# Sheet_1_2024-06-24.net
KiCad netlist of a schematic drawn in Altium Designer
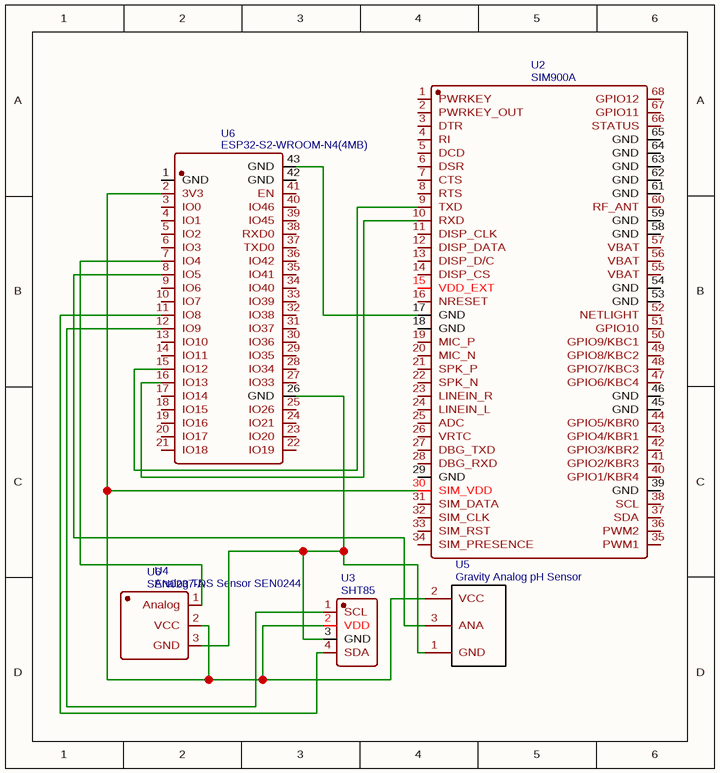
[diagram p0: Sheet_1_2024-06-24.schdoc]

(export (version "E")
  (design (tool "Eeschema 10.0.6"))
  (components
    (comp (ref "U2")
      (value "SIM900A")
      (fields (field (name "CONTRIBUTOR") "LCSC"))
      (libsource (lib "altium-import") (part "root_0_SIM900A_"))
    )
    (comp (ref "U3")
      (value "SHT85")
      (fields (field (name "CONTRIBUTOR") "zsamora"))
      (libsource (lib "altium-import") (part "root_0_SHT85_"))
    )
    (comp (ref "U4")
      (value "Analog TDS Sensor SEN0244")
      (fields (field (name "CONTRIBUTOR") "陳詩函"))
      (libsource (lib "altium-import") (part "root_0_Analog TDS Sensor SEN0244_"))
    )
    (comp (ref "U5")
      (value "Gravity Analog pH Sensor")
      (fields
        (field (name "MANUFACTURER") "Atlas Scientific")
        (field (name "MANUFACTURER PART") "GRV-pH")
        (field (name "CONTRIBUTOR") "ajannin82")
      )
      (libsource (lib "altium-import") (part "root_0_Gravity Analog pH Sensor_"))
    )
    (comp (ref "U6")
      (value "ESP32-S2-WROOM-N4(4MB)")
      (fields (field (name "MANUFACTURER") "ESPRESSIF(乐鑫)") (field (name "CONTRIBUTOR") "lcsc"))
      (libsource (lib "altium-import") (part "root_0_ESP32-S2-WROOM-N4(4MB)_"))
    )
  )
  (nets
    (net (code "1") (name "Net-(U2-GND-Pad17)") (class "Default")
      (node (ref "U2") (pin "17") (pinfunction "GND_17") (pintype "passive"))
      (node (ref "U6") (pin "43") (pinfunction "GND_43") (pintype "passive"))
    )
    (net (code "2") (name "Net-(U2-RXD)") (class "Default")
      (node (ref "U2") (pin "10") (pinfunction "RXD_10") (pintype "passive"))
      (node (ref "U6") (pin "16") (pinfunction "IO13_16") (pintype "passive"))
    )
    (net (code "3") (name "Net-(U2-SIM_VDD)") (class "Default")
      (node (ref "U2") (pin "30") (pinfunction "SIM_VDD_30") (pintype "passive"))
      (node (ref "U3") (pin "2") (pinfunction "VDD_2") (pintype "passive"))
      (node (ref "U4") (pin "2") (pinfunction "VCC_2") (pintype "passive"))
      (node (ref "U5") (pin "2") (pinfunction "VCC_2") (pintype "passive"))
      (node (ref "U6") (pin "2") (pinfunction "3V3_2") (pintype "passive"))
    )
    (net (code "4") (name "Net-(U2-TXD)") (class "Default")
      (node (ref "U2") (pin "9") (pinfunction "TXD_9") (pintype "passive"))
      (node (ref "U6") (pin "15") (pinfunction "IO12_15") (pintype "passive"))
    )
    (net (code "5") (name "Net-(U3-GND)") (class "Default")
      (node (ref "U3") (pin "3") (pinfunction "GND_3") (pintype "passive"))
      (node (ref "U4") (pin "3") (pinfunction "GND_3") (pintype "passive"))
      (node (ref "U5") (pin "1") (pinfunction "GND_1") (pintype "passive"))
      (node (ref "U6") (pin "26") (pinfunction "GND_26") (pintype "passive"))
    )
    (net (code "6") (name "Net-(U3-SCL)") (class "Default")
      (node (ref "U3") (pin "1") (pinfunction "SCL_1") (pintype "passive"))
      (node (ref "U6") (pin "12") (pinfunction "IO9_12") (pintype "passive"))
    )
    (net (code "7") (name "Net-(U3-SDA)") (class "Default")
      (node (ref "U3") (pin "4") (pinfunction "SDA_4") (pintype "passive"))
      (node (ref "U6") (pin "11") (pinfunction "IO8_11") (pintype "passive"))
    )
    (net (code "8") (name "Net-(U4-Analog)") (class "Default")
      (node (ref "U4") (pin "1") (pinfunction "Analog_1") (pintype "passive"))
      (node (ref "U6") (pin "7") (pinfunction "IO4_7") (pintype "passive"))
    )
    (net (code "9") (name "Net-(U5-ANA)") (class "Default")
      (node (ref "U5") (pin "3") (pinfunction "ANA_3") (pintype "passive"))
      (node (ref "U6") (pin "8") (pinfunction "IO5_8") (pintype "passive"))
    )
    (net (code "10") (name "unconnected-(U2-ADC-Pad25)") (class "Default")
      (node (ref "U2") (pin "25") (pinfunction "ADC_25") (pintype "passive"))
    )
    (net (code "11") (name "unconnected-(U2-CTS-Pad7)") (class "Default")
      (node (ref "U2") (pin "7") (pinfunction "CTS_7") (pintype "passive"))
    )
    (net (code "12") (name "unconnected-(U2-DBG_RXD-Pad28)") (class "Default")
      (node (ref "U2") (pin "28") (pinfunction "DBG_RXD_28") (pintype "passive"))
    )
    (net (code "13") (name "unconnected-(U2-DBG_TXD-Pad27)") (class "Default")
      (node (ref "U2") (pin "27") (pinfunction "DBG_TXD_27") (pintype "passive"))
    )
    (net (code "14") (name "unconnected-(U2-DCD-Pad5)") (class "Default")
      (node (ref "U2") (pin "5") (pinfunction "DCD_5") (pintype "passive"))
    )
    (net (code "15") (name "unconnected-(U2-DISP_CLK-Pad11)") (class "Default")
      (node (ref "U2") (pin "11") (pinfunction "DISP_CLK_11") (pintype "passive"))
    )
    (net (code "16") (name "unconnected-(U2-DISP_CS-Pad14)") (class "Default")
      (node (ref "U2") (pin "14") (pinfunction "DISP_CS_14") (pintype "passive"))
    )
    (net (code "17") (name "unconnected-(U2-DISP_DATA-Pad12)") (class "Default")
      (node (ref "U2") (pin "12") (pinfunction "DISP_DATA_12") (pintype "passive"))
    )
    (net (code "18") (name "unconnected-(U2-DISP_D{slash}C-Pad13)") (class "Default")
      (node (ref "U2") (pin "13") (pinfunction "DISP_D/C_13") (pintype "passive"))
    )
    (net (code "19") (name "unconnected-(U2-DSR-Pad6)") (class "Default")
      (node (ref "U2") (pin "6") (pinfunction "DSR_6") (pintype "passive"))
    )
    (net (code "20") (name "unconnected-(U2-DTR-Pad3)") (class "Default")
      (node (ref "U2") (pin "3") (pinfunction "DTR_3") (pintype "passive"))
    )
    (net (code "21") (name "unconnected-(U2-GND-Pad18)") (class "Default")
      (node (ref "U2") (pin "18") (pinfunction "GND_18") (pintype "passive"))
    )
    (net (code "22") (name "unconnected-(U2-GND-Pad29)") (class "Default")
      (node (ref "U2") (pin "29") (pinfunction "GND_29") (pintype "passive"))
    )
    (net (code "23") (name "unconnected-(U2-GND-Pad39)") (class "Default")
      (node (ref "U2") (pin "39") (pinfunction "GND_39") (pintype "passive"))
    )
    (net (code "24") (name "unconnected-(U2-GND-Pad45)") (class "Default")
      (node (ref "U2") (pin "45") (pinfunction "GND_45") (pintype "passive"))
    )
    (net (code "25") (name "unconnected-(U2-GND-Pad46)") (class "Default")
      (node (ref "U2") (pin "46") (pinfunction "GND_46") (pintype "passive"))
    )
    (net (code "26") (name "unconnected-(U2-GND-Pad53)") (class "Default")
      (node (ref "U2") (pin "53") (pinfunction "GND_53") (pintype "passive"))
    )
    (net (code "27") (name "unconnected-(U2-GND-Pad54)") (class "Default")
      (node (ref "U2") (pin "54") (pinfunction "GND_54") (pintype "passive"))
    )
    (net (code "28") (name "unconnected-(U2-GND-Pad58)") (class "Default")
      (node (ref "U2") (pin "58") (pinfunction "GND_58") (pintype "passive"))
    )
    (net (code "29") (name "unconnected-(U2-GND-Pad59)") (class "Default")
      (node (ref "U2") (pin "59") (pinfunction "GND_59") (pintype "passive"))
    )
    (net (code "30") (name "unconnected-(U2-GND-Pad61)") (class "Default")
      (node (ref "U2") (pin "61") (pinfunction "GND_61") (pintype "passive"))
    )
    (net (code "31") (name "unconnected-(U2-GND-Pad62)") (class "Default")
      (node (ref "U2") (pin "62") (pinfunction "GND_62") (pintype "passive"))
    )
    (net (code "32") (name "unconnected-(U2-GND-Pad63)") (class "Default")
      (node (ref "U2") (pin "63") (pinfunction "GND_63") (pintype "passive"))
    )
    (net (code "33") (name "unconnected-(U2-GND-Pad64)") (class "Default")
      (node (ref "U2") (pin "64") (pinfunction "GND_64") (pintype "passive"))
    )
    (net (code "34") (name "unconnected-(U2-GND-Pad65)") (class "Default")
      (node (ref "U2") (pin "65") (pinfunction "GND_65") (pintype "passive"))
    )
    (net (code "35") (name "unconnected-(U2-GPIO1{slash}KBR4-Pad40)") (class "Default")
      (node (ref "U2") (pin "40") (pinfunction "GPIO1/KBR4_40") (pintype "passive"))
    )
    (net (code "36") (name "unconnected-(U2-GPIO2{slash}KBR3-Pad41)") (class "Default")
      (node (ref "U2") (pin "41") (pinfunction "GPIO2/KBR3_41") (pintype "passive"))
    )
    (net (code "37") (name "unconnected-(U2-GPIO3{slash}KBR2-Pad42)") (class "Default")
      (node (ref "U2") (pin "42") (pinfunction "GPIO3/KBR2_42") (pintype "passive"))
    )
    (net (code "38") (name "unconnected-(U2-GPIO4{slash}KBR1-Pad43)") (class "Default")
      (node (ref "U2") (pin "43") (pinfunction "GPIO4/KBR1_43") (pintype "passive"))
    )
    (net (code "39") (name "unconnected-(U2-GPIO5{slash}KBR0-Pad44)") (class "Default")
      (node (ref "U2") (pin "44") (pinfunction "GPIO5/KBR0_44") (pintype "passive"))
    )
    (net (code "40") (name "unconnected-(U2-GPIO6{slash}KBC4-Pad47)") (class "Default")
      (node (ref "U2") (pin "47") (pinfunction "GPIO6/KBC4_47") (pintype "passive"))
    )
    (net (code "41") (name "unconnected-(U2-GPIO7{slash}KBC3-Pad48)") (class "Default")
      (node (ref "U2") (pin "48") (pinfunction "GPIO7/KBC3_48") (pintype "passive"))
    )
    (net (code "42") (name "unconnected-(U2-GPIO8{slash}KBC2-Pad49)") (class "Default")
      (node (ref "U2") (pin "49") (pinfunction "GPIO8/KBC2_49") (pintype "passive"))
    )
    (net (code "43") (name "unconnected-(U2-GPIO9{slash}KBC1-Pad50)") (class "Default")
      (node (ref "U2") (pin "50") (pinfunction "GPIO9/KBC1_50") (pintype "passive"))
    )
    (net (code "44") (name "unconnected-(U2-GPIO10-Pad51)") (class "Default")
      (node (ref "U2") (pin "51") (pinfunction "GPIO10_51") (pintype "passive"))
    )
    (net (code "45") (name "unconnected-(U2-GPIO11-Pad67)") (class "Default")
      (node (ref "U2") (pin "67") (pinfunction "GPIO11_67") (pintype "passive"))
    )
    (net (code "46") (name "unconnected-(U2-GPIO12-Pad68)") (class "Default")
      (node (ref "U2") (pin "68") (pinfunction "GPIO12_68") (pintype "passive"))
    )
    (net (code "47") (name "unconnected-(U2-LINEIN_L-Pad24)") (class "Default")
      (node (ref "U2") (pin "24") (pinfunction "LINEIN_L_24") (pintype "passive"))
    )
    (net (code "48") (name "unconnected-(U2-LINEIN_R-Pad23)") (class "Default")
      (node (ref "U2") (pin "23") (pinfunction "LINEIN_R_23") (pintype "passive"))
    )
    (net (code "49") (name "unconnected-(U2-MIC_N-Pad20)") (class "Default")
      (node (ref "U2") (pin "20") (pinfunction "MIC_N_20") (pintype "passive"))
    )
    (net (code "50") (name "unconnected-(U2-MIC_P-Pad19)") (class "Default")
      (node (ref "U2") (pin "19") (pinfunction "MIC_P_19") (pintype "passive"))
    )
    (net (code "51") (name "unconnected-(U2-NETLIGHT-Pad52)") (class "Default")
      (node (ref "U2") (pin "52") (pinfunction "NETLIGHT_52") (pintype "passive"))
    )
    (net (code "52") (name "unconnected-(U2-NRESET-Pad16)") (class "Default")
      (node (ref "U2") (pin "16") (pinfunction "NRESET_16") (pintype "passive"))
    )
    (net (code "53") (name "unconnected-(U2-PWM1-Pad35)") (class "Default")
      (node (ref "U2") (pin "35") (pinfunction "PWM1_35") (pintype "passive"))
    )
    (net (code "54") (name "unconnected-(U2-PWM2-Pad36)") (class "Default")
      (node (ref "U2") (pin "36") (pinfunction "PWM2_36") (pintype "passive"))
    )
    (net (code "55") (name "unconnected-(U2-PWRKEY-Pad1)") (class "Default")
      (node (ref "U2") (pin "1") (pinfunction "PWRKEY_1") (pintype "passive"))
    )
    (net (code "56") (name "unconnected-(U2-PWRKEY_OUT-Pad2)") (class "Default")
      (node (ref "U2") (pin "2") (pinfunction "PWRKEY_OUT_2") (pintype "passive"))
    )
    (net (code "57") (name "unconnected-(U2-RF_ANT-Pad60)") (class "Default")
      (node (ref "U2") (pin "60") (pinfunction "RF_ANT_60") (pintype "passive"))
    )
    (net (code "58") (name "unconnected-(U2-RI-Pad4)") (class "Default")
      (node (ref "U2") (pin "4") (pinfunction "RI_4") (pintype "passive"))
    )
    (net (code "59") (name "unconnected-(U2-RTS-Pad8)") (class "Default")
      (node (ref "U2") (pin "8") (pinfunction "RTS_8") (pintype "passive"))
    )
    (net (code "60") (name "unconnected-(U2-SCL-Pad38)") (class "Default")
      (node (ref "U2") (pin "38") (pinfunction "SCL_38") (pintype "passive"))
    )
    (net (code "61") (name "unconnected-(U2-SDA-Pad37)") (class "Default")
      (node (ref "U2") (pin "37") (pinfunction "SDA_37") (pintype "passive"))
    )
    (net (code "62") (name "unconnected-(U2-SIM_CLK-Pad32)") (class "Default")
      (node (ref "U2") (pin "32") (pinfunction "SIM_CLK_32") (pintype "passive"))
    )
    (net (code "63") (name "unconnected-(U2-SIM_DATA-Pad31)") (class "Default")
      (node (ref "U2") (pin "31") (pinfunction "SIM_DATA_31") (pintype "passive"))
    )
    (net (code "64") (name "unconnected-(U2-SIM_PRESENCE-Pad34)") (class "Default")
      (node (ref "U2") (pin "34") (pinfunction "SIM_PRESENCE_34") (pintype "passive"))
    )
    (net (code "65") (name "unconnected-(U2-SIM_RST-Pad33)") (class "Default")
      (node (ref "U2") (pin "33") (pinfunction "SIM_RST_33") (pintype "passive"))
    )
    (net (code "66") (name "unconnected-(U2-SPK_N-Pad22)") (class "Default")
      (node (ref "U2") (pin "22") (pinfunction "SPK_N_22") (pintype "passive"))
    )
    (net (code "67") (name "unconnected-(U2-SPK_P-Pad21)") (class "Default")
      (node (ref "U2") (pin "21") (pinfunction "SPK_P_21") (pintype "passive"))
    )
    (net (code "68") (name "unconnected-(U2-STATUS-Pad66)") (class "Default")
      (node (ref "U2") (pin "66") (pinfunction "STATUS_66") (pintype "passive"))
    )
    (net (code "69") (name "unconnected-(U2-VBAT-Pad55)") (class "Default")
      (node (ref "U2") (pin "55") (pinfunction "VBAT_55") (pintype "passive"))
    )
    (net (code "70") (name "unconnected-(U2-VBAT-Pad56)") (class "Default")
      (node (ref "U2") (pin "56") (pinfunction "VBAT_56") (pintype "passive"))
    )
    (net (code "71") (name "unconnected-(U2-VBAT-Pad57)") (class "Default")
      (node (ref "U2") (pin "57") (pinfunction "VBAT_57") (pintype "passive"))
    )
    (net (code "72") (name "unconnected-(U2-VDD_EXT-Pad15)") (class "Default")
      (node (ref "U2") (pin "15") (pinfunction "VDD_EXT_15") (pintype "passive"))
    )
    (net (code "73") (name "unconnected-(U2-VRTC-Pad26)") (class "Default")
      (node (ref "U2") (pin "26") (pinfunction "VRTC_26") (pintype "passive"))
    )
    (net (code "74") (name "unconnected-(U6-EN-Pad41)") (class "Default")
      (node (ref "U6") (pin "41") (pinfunction "EN_41") (pintype "passive"))
    )
    (net (code "75") (name "unconnected-(U6-GND-Pad1)") (class "Default")
      (node (ref "U6") (pin "1") (pinfunction "GND_1") (pintype "passive"))
    )
    (net (code "76") (name "unconnected-(U6-GND-Pad42)") (class "Default")
      (node (ref "U6") (pin "42") (pinfunction "GND_42") (pintype "passive"))
    )
    (net (code "77") (name "unconnected-(U6-IO0-Pad3)") (class "Default")
      (node (ref "U6") (pin "3") (pinfunction "IO0_3") (pintype "passive"))
    )
    (net (code "78") (name "unconnected-(U6-IO1-Pad4)") (class "Default")
      (node (ref "U6") (pin "4") (pinfunction "IO1_4") (pintype "passive"))
    )
    (net (code "79") (name "unconnected-(U6-IO2-Pad5)") (class "Default")
      (node (ref "U6") (pin "5") (pinfunction "IO2_5") (pintype "passive"))
    )
    (net (code "80") (name "unconnected-(U6-IO3-Pad6)") (class "Default")
      (node (ref "U6") (pin "6") (pinfunction "IO3_6") (pintype "passive"))
    )
    (net (code "81") (name "unconnected-(U6-IO6-Pad9)") (class "Default")
      (node (ref "U6") (pin "9") (pinfunction "IO6_9") (pintype "passive"))
    )
    (net (code "82") (name "unconnected-(U6-IO7-Pad10)") (class "Default")
      (node (ref "U6") (pin "10") (pinfunction "IO7_10") (pintype "passive"))
    )
    (net (code "83") (name "unconnected-(U6-IO10-Pad13)") (class "Default")
      (node (ref "U6") (pin "13") (pinfunction "IO10_13") (pintype "passive"))
    )
    (net (code "84") (name "unconnected-(U6-IO11-Pad14)") (class "Default")
      (node (ref "U6") (pin "14") (pinfunction "IO11_14") (pintype "passive"))
    )
    (net (code "85") (name "unconnected-(U6-IO14-Pad17)") (class "Default")
      (node (ref "U6") (pin "17") (pinfunction "IO14_17") (pintype "passive"))
    )
    (net (code "86") (name "unconnected-(U6-IO15-Pad18)") (class "Default")
      (node (ref "U6") (pin "18") (pinfunction "IO15_18") (pintype "passive"))
    )
    (net (code "87") (name "unconnected-(U6-IO16-Pad19)") (class "Default")
      (node (ref "U6") (pin "19") (pinfunction "IO16_19") (pintype "passive"))
    )
    (net (code "88") (name "unconnected-(U6-IO17-Pad20)") (class "Default")
      (node (ref "U6") (pin "20") (pinfunction "IO17_20") (pintype "passive"))
    )
    (net (code "89") (name "unconnected-(U6-IO18-Pad21)") (class "Default")
      (node (ref "U6") (pin "21") (pinfunction "IO18_21") (pintype "passive"))
    )
    (net (code "90") (name "unconnected-(U6-IO19-Pad22)") (class "Default")
      (node (ref "U6") (pin "22") (pinfunction "IO19_22") (pintype "passive"))
    )
    (net (code "91") (name "unconnected-(U6-IO20-Pad23)") (class "Default")
      (node (ref "U6") (pin "23") (pinfunction "IO20_23") (pintype "passive"))
    )
    (net (code "92") (name "unconnected-(U6-IO21-Pad24)") (class "Default")
      (node (ref "U6") (pin "24") (pinfunction "IO21_24") (pintype "passive"))
    )
    (net (code "93") (name "unconnected-(U6-IO26-Pad25)") (class "Default")
      (node (ref "U6") (pin "25") (pinfunction "IO26_25") (pintype "passive"))
    )
    (net (code "94") (name "unconnected-(U6-IO33-Pad27)") (class "Default")
      (node (ref "U6") (pin "27") (pinfunction "IO33_27") (pintype "passive"))
    )
    (net (code "95") (name "unconnected-(U6-IO34-Pad28)") (class "Default")
      (node (ref "U6") (pin "28") (pinfunction "IO34_28") (pintype "passive"))
    )
    (net (code "96") (name "unconnected-(U6-IO35-Pad29)") (class "Default")
      (node (ref "U6") (pin "29") (pinfunction "IO35_29") (pintype "passive"))
    )
    (net (code "97") (name "unconnected-(U6-IO36-Pad30)") (class "Default")
      (node (ref "U6") (pin "30") (pinfunction "IO36_30") (pintype "passive"))
    )
    (net (code "98") (name "unconnected-(U6-IO37-Pad31)") (class "Default")
      (node (ref "U6") (pin "31") (pinfunction "IO37_31") (pintype "passive"))
    )
    (net (code "99") (name "unconnected-(U6-IO38-Pad32)") (class "Default")
      (node (ref "U6") (pin "32") (pinfunction "IO38_32") (pintype "passive"))
    )
    (net (code "100") (name "unconnected-(U6-IO39-Pad33)") (class "Default")
      (node (ref "U6") (pin "33") (pinfunction "IO39_33") (pintype "passive"))
    )
    (net (code "101") (name "unconnected-(U6-IO40-Pad34)") (class "Default")
      (node (ref "U6") (pin "34") (pinfunction "IO40_34") (pintype "passive"))
    )
    (net (code "102") (name "unconnected-(U6-IO41-Pad35)") (class "Default")
      (node (ref "U6") (pin "35") (pinfunction "IO41_35") (pintype "passive"))
    )
    (net (code "103") (name "unconnected-(U6-IO42-Pad36)") (class "Default")
      (node (ref "U6") (pin "36") (pinfunction "IO42_36") (pintype "passive"))
    )
    (net (code "104") (name "unconnected-(U6-IO45-Pad39)") (class "Default")
      (node (ref "U6") (pin "39") (pinfunction "IO45_39") (pintype "passive"))
    )
    (net (code "105") (name "unconnected-(U6-IO46-Pad40)") (class "Default")
      (node (ref "U6") (pin "40") (pinfunction "IO46_40") (pintype "passive"))
    )
    (net (code "106") (name "unconnected-(U6-RXD0-Pad38)") (class "Default")
      (node (ref "U6") (pin "38") (pinfunction "RXD0_38") (pintype "passive"))
    )
    (net (code "107") (name "unconnected-(U6-TXD0-Pad37)") (class "Default")
      (node (ref "U6") (pin "37") (pinfunction "TXD0_37") (pintype "passive"))
    )
  )
)
